# Versie_1.net
KiCad netlist of a schematic drawn in EAGLE
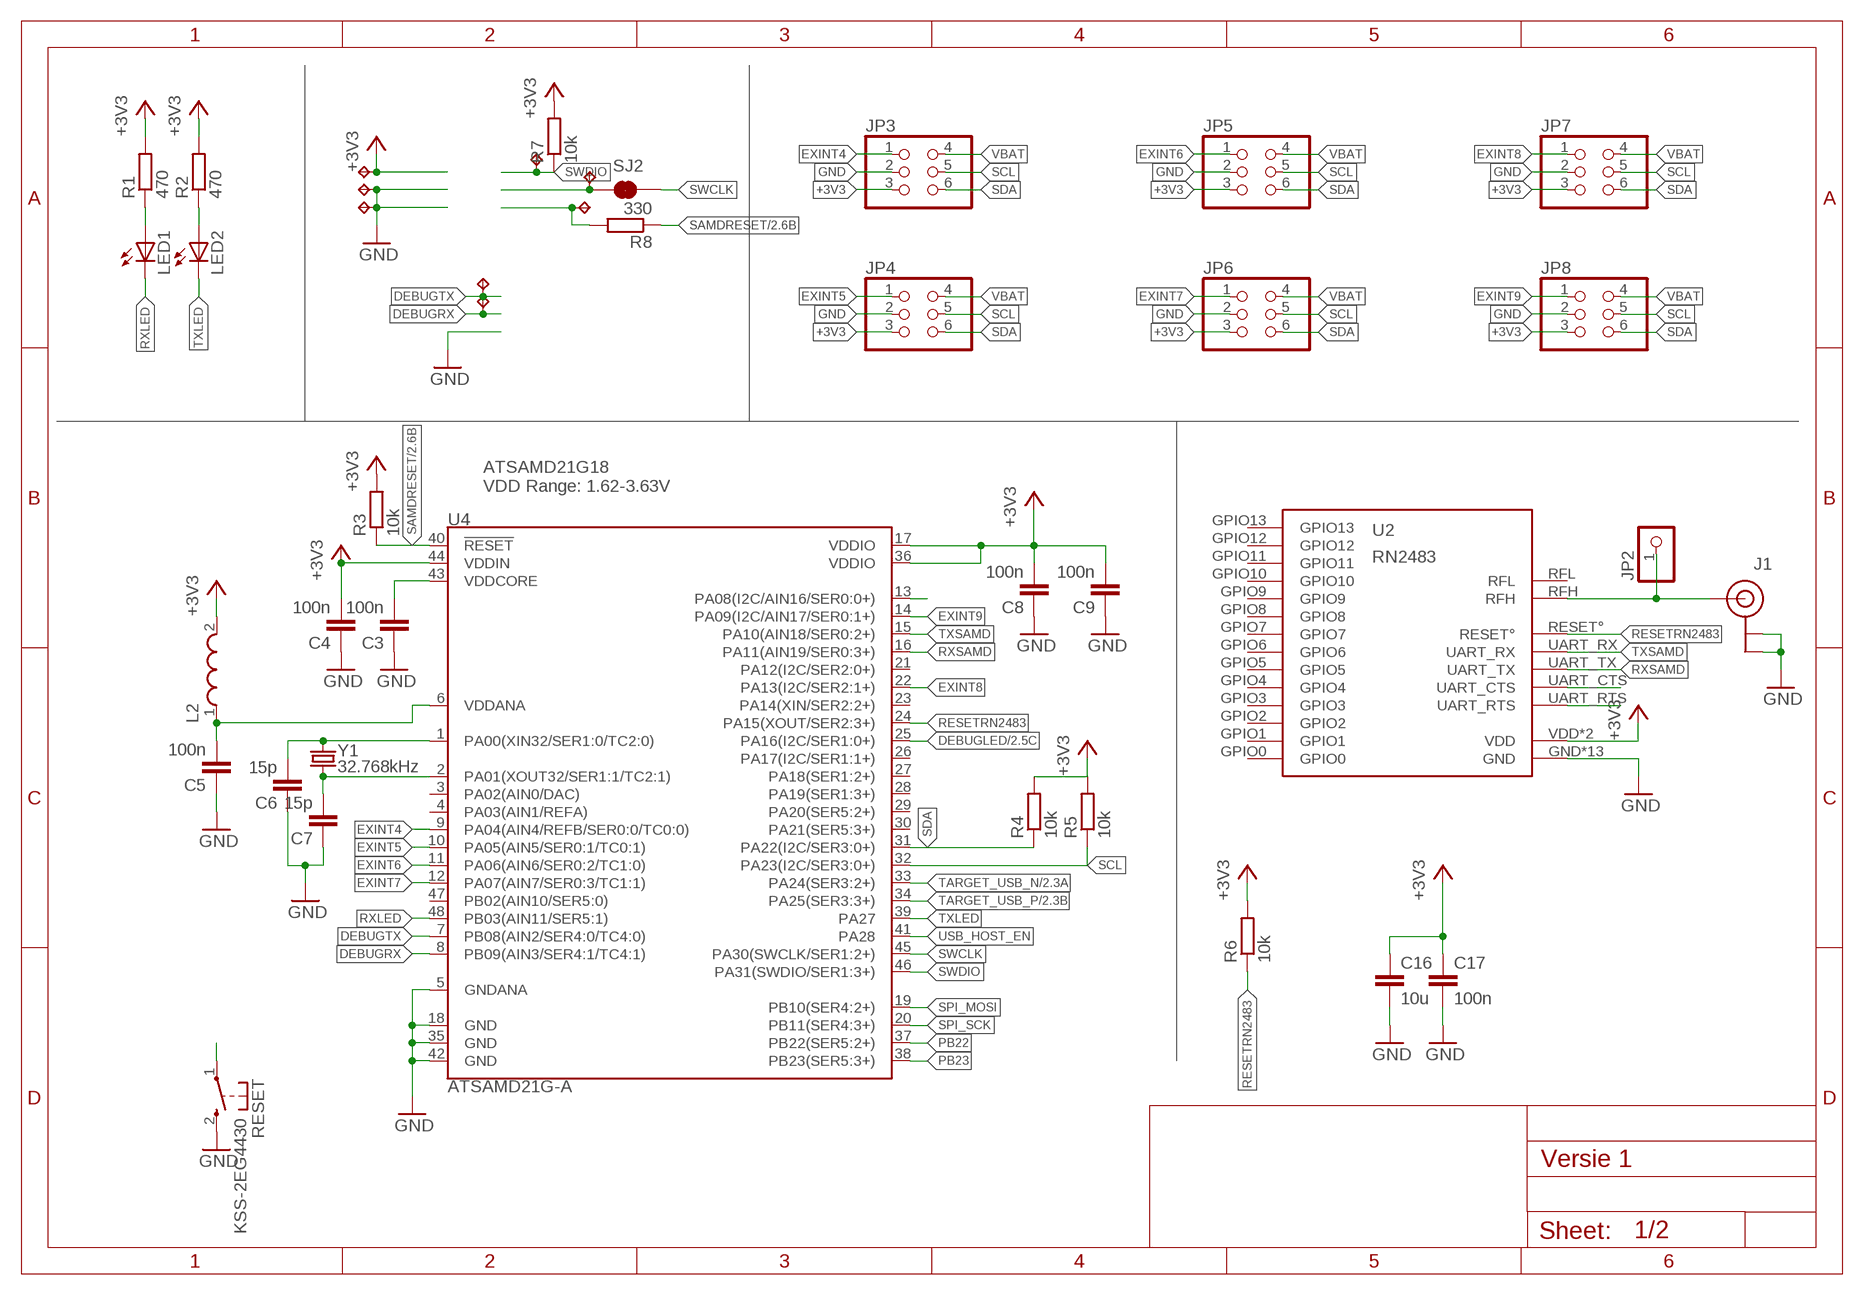
[diagram p0: schematic, sheet 1]
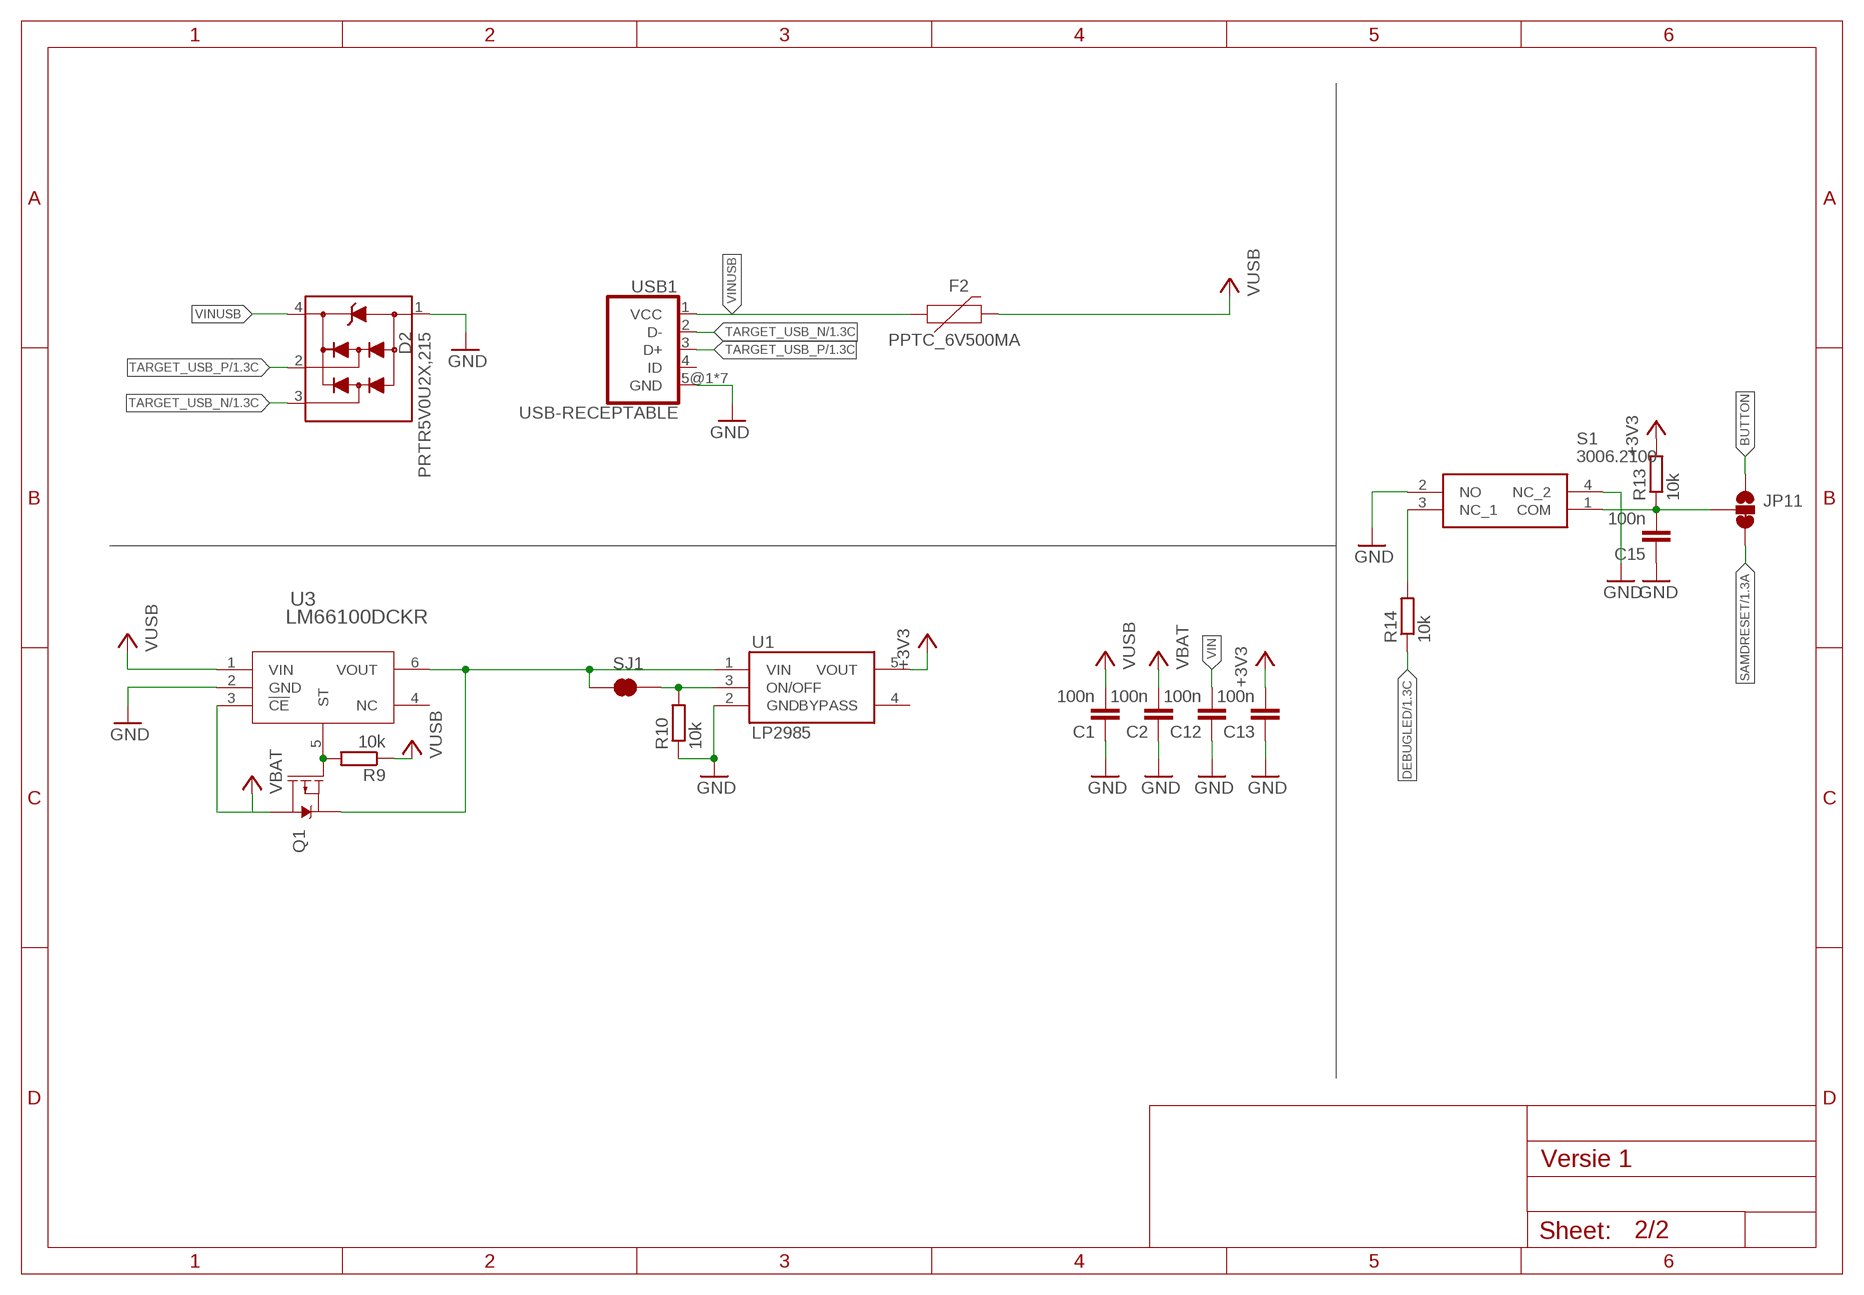
[diagram p1: schematic, sheet 2]

(export (version "E")
  (design (tool "Eeschema 10.0.6"))
  (components
    (comp (ref "C1")
      (value "100n")
      (footprint "eagle-import:C0603")
      (libsource (lib "eagle-import") (part "C-EUC0603"))
    )
    (comp (ref "C2")
      (value "100n")
      (footprint "eagle-import:C0603")
      (libsource (lib "eagle-import") (part "C-EUC0603"))
    )
    (comp (ref "C12")
      (value "100n")
      (footprint "eagle-import:C0603")
      (libsource (lib "eagle-import") (part "C-EUC0603"))
    )
    (comp (ref "C13")
      (value "100n")
      (footprint "eagle-import:C0603")
      (libsource (lib "eagle-import") (part "C-EUC0603"))
    )
    (comp (ref "C15")
      (value "100n")
      (footprint "eagle-import:C0603")
      (libsource (lib "eagle-import") (part "C-EUC0603"))
    )
    (comp (ref "D2")
      (value "PRTR5V0U2X,215")
      (footprint "eagle-import:SOT143B")
      (fields (field (name "MF") "Nexperia USA Inc."))
      (libsource (lib "eagle-import") (part "PRTR5V0U2X,215"))
    )
    (comp (ref "F2")
      (value "PPTC_6V500MA")
      (footprint "eagle-import:0805")
      (libsource (lib "eagle-import") (part "PPTC_6V500MA"))
    )
    (comp (ref "JP11")
      (value "JUMPER-SMT_3_1-NC_TRACE_SILK")
      (footprint "eagle-import:SMT-JUMPER_3_1-NC_TRACE_SILK")
      (libsource (lib "eagle-import") (part "JUMPER-SMT_3_1-NC_TRACE_SILK"))
    )
    (comp (ref "Q1")
      (value "MOSFET_PCH-DMG2307L")
      (footprint "eagle-import:SOT23-3")
      (libsource (lib "eagle-import") (part "MOSFET_PCH-DMG2307L"))
    )
    (comp (ref "R9")
      (value "10k")
      (footprint "eagle-import:R0603")
      (libsource (lib "eagle-import") (part "R-EU_R0603"))
    )
    (comp (ref "R10")
      (value "10k")
      (footprint "eagle-import:R0603")
      (libsource (lib "eagle-import") (part "R-EU_R0603"))
    )
    (comp (ref "R13")
      (value "10k")
      (footprint "eagle-import:R0603")
      (libsource (lib "eagle-import") (part "R-EU_R0603"))
    )
    (comp (ref "R14")
      (value "10k")
      (footprint "eagle-import:R0603")
      (libsource (lib "eagle-import") (part "R-EU_R0603"))
    )
    (comp (ref "S1")
      (value "3006.2100")
      (footprint "eagle-import:30062101")
      (fields (field (name "MOUSER_PART_NUMBER") "979-3006.2100"))
      (libsource (lib "eagle-import") (part "3006.2100"))
    )
    (comp (ref "SJ1")
      (value "JUMPER-PAD-2-NC_BY_TRACENO_SILK")
      (footprint "eagle-import:PAD-JUMPER-2-NC_BY_TRACE_NO_SILK")
      (libsource (lib "eagle-import") (part "JUMPER-PAD-2-NC_BY_TRACENO_SILK"))
    )
    (comp (ref "U1")
      (value "LP2985AIM5-3.3")
      (footprint "eagle-import:SOT25")
      (libsource (lib "eagle-import") (part "LP2985AIM5-3.3"))
    )
    (comp (ref "U3")
      (value "LM66100DCKR")
      (footprint "eagle-import:DCK6_TEX")
      (fields (field (name "COPYRIGHT") "Copyright (C) 2018 Accelerated Designs. All rights reserved"))
      (libsource (lib "eagle-import") (part "LM66100DCKR"))
    )
    (comp (ref "USB1")
      (value "USB-RECEPTABLE")
      (footprint "eagle-import:FCI-10103594-0001LF")
      (libsource (lib "eagle-import") (part "USB-RECEPTABLE"))
    )
    (comp (ref "C3")
      (value "100n")
      (footprint "eagle-import:C0603")
      (libsource (lib "eagle-import") (part "C-EUC0603"))
    )
    (comp (ref "C4")
      (value "100n")
      (footprint "eagle-import:C0603")
      (libsource (lib "eagle-import") (part "C-EUC0603"))
    )
    (comp (ref "C5")
      (value "100n")
      (footprint "eagle-import:C0603")
      (libsource (lib "eagle-import") (part "C-EUC0603"))
    )
    (comp (ref "C6")
      (value "15p")
      (footprint "eagle-import:C0603")
      (libsource (lib "eagle-import") (part "C-EUC0603"))
    )
    (comp (ref "C7")
      (value "15p")
      (footprint "eagle-import:C0603")
      (libsource (lib "eagle-import") (part "C-EUC0603"))
    )
    (comp (ref "C8")
      (value "100n")
      (footprint "eagle-import:C0603")
      (libsource (lib "eagle-import") (part "C-EUC0603"))
    )
    (comp (ref "C9")
      (value "100n")
      (footprint "eagle-import:C0603")
      (libsource (lib "eagle-import") (part "C-EUC0603"))
    )
    (comp (ref "C16")
      (value "10u")
      (footprint "eagle-import:C0805")
      (libsource (lib "eagle-import") (part "C-EUC0805"))
    )
    (comp (ref "C17")
      (value "100n")
      (footprint "eagle-import:C0603")
      (libsource (lib "eagle-import") (part "C-EUC0603"))
    )
    (comp (ref "J1")
      (value "U.FL")
      (footprint "eagle-import:U.FL")
      (libsource (lib "eagle-import") (part "U.FL"))
    )
    (comp (ref "JP2")
      (value "PINHD-1X1")
      (footprint "eagle-import:1X01")
      (libsource (lib "eagle-import") (part "PINHD-1X1"))
    )
    (comp (ref "JP3")
      (value "PINHD-2X3")
      (footprint "eagle-import:2X03")
      (libsource (lib "eagle-import") (part "PINHD-2X3"))
    )
    (comp (ref "JP4")
      (value "PINHD-2X3")
      (footprint "eagle-import:2X03")
      (libsource (lib "eagle-import") (part "PINHD-2X3"))
    )
    (comp (ref "JP5")
      (value "PINHD-2X3")
      (footprint "eagle-import:2X03")
      (libsource (lib "eagle-import") (part "PINHD-2X3"))
    )
    (comp (ref "JP6")
      (value "PINHD-2X3")
      (footprint "eagle-import:2X03")
      (libsource (lib "eagle-import") (part "PINHD-2X3"))
    )
    (comp (ref "JP7")
      (value "PINHD-2X3")
      (footprint "eagle-import:2X03")
      (libsource (lib "eagle-import") (part "PINHD-2X3"))
    )
    (comp (ref "JP8")
      (value "PINHD-2X3")
      (footprint "eagle-import:2X03")
      (libsource (lib "eagle-import") (part "PINHD-2X3"))
    )
    (comp (ref "L2")
      (value "WE-CBA_0603(WB/HS)")
      (footprint "eagle-import:WE-CBA_0603(W=2.2)")
      (libsource (lib "eagle-import") (part "WE-CBA_0603(WB/HS)"))
    )
    (comp (ref "LED1")
      (value "LEDCHIP-LED0603")
      (footprint "eagle-import:CHIP-LED0603")
      (libsource (lib "eagle-import") (part "LEDCHIP-LED0603"))
    )
    (comp (ref "LED2")
      (value "LEDCHIP-LED0603")
      (footprint "eagle-import:CHIP-LED0603")
      (libsource (lib "eagle-import") (part "LEDCHIP-LED0603"))
    )
    (comp (ref "R1")
      (value "470")
      (footprint "eagle-import:R0603")
      (libsource (lib "eagle-import") (part "R-EU_R0603"))
    )
    (comp (ref "R2")
      (value "470")
      (footprint "eagle-import:R0603")
      (libsource (lib "eagle-import") (part "R-EU_R0603"))
    )
    (comp (ref "R3")
      (value "10k")
      (footprint "eagle-import:R0603")
      (libsource (lib "eagle-import") (part "R-EU_R0603"))
    )
    (comp (ref "R4")
      (value "10k")
      (footprint "eagle-import:R0603")
      (libsource (lib "eagle-import") (part "R-EU_R0603"))
    )
    (comp (ref "R5")
      (value "10k")
      (footprint "eagle-import:R0603")
      (libsource (lib "eagle-import") (part "R-EU_R0603"))
    )
    (comp (ref "R6")
      (value "10k")
      (footprint "eagle-import:R0603")
      (libsource (lib "eagle-import") (part "R-EU_R0603"))
    )
    (comp (ref "R7")
      (value "10k")
      (footprint "eagle-import:R0603")
      (libsource (lib "eagle-import") (part "R-EU_R0603"))
    )
    (comp (ref "R8")
      (value "330")
      (footprint "eagle-import:R0603")
      (libsource (lib "eagle-import") (part "R-EU_R0603"))
    )
    (comp (ref "RESET")
      (value "KSS-2EG4430")
      (footprint "eagle-import:KSS-2EG4430")
      (libsource (lib "eagle-import") (part "KSS-2EG4430"))
    )
    (comp (ref "SJ2")
      (value "JUMPER-PAD-2-NC_BY_TRACENO_SILK")
      (footprint "eagle-import:PAD-JUMPER-2-NC_BY_TRACE_NO_SILK")
      (libsource (lib "eagle-import") (part "JUMPER-PAD-2-NC_BY_TRACENO_SILK"))
    )
    (comp (ref "TP1")
      (value "TPB1,27")
      (footprint "eagle-import:B1,27")
      (libsource (lib "eagle-import") (part "TPB1,27"))
    )
    (comp (ref "TP2")
      (value "TPB1,27")
      (footprint "eagle-import:B1,27")
      (libsource (lib "eagle-import") (part "TPB1,27"))
    )
    (comp (ref "TP3")
      (value "TPB1,27")
      (footprint "eagle-import:B1,27")
      (libsource (lib "eagle-import") (part "TPB1,27"))
    )
    (comp (ref "TP4")
      (value "TPB1,27")
      (footprint "eagle-import:B1,27")
      (libsource (lib "eagle-import") (part "TPB1,27"))
    )
    (comp (ref "TP5")
      (value "TPB1,27")
      (footprint "eagle-import:B1,27")
      (libsource (lib "eagle-import") (part "TPB1,27"))
    )
    (comp (ref "TP6")
      (value "TPB1,27")
      (footprint "eagle-import:B1,27")
      (libsource (lib "eagle-import") (part "TPB1,27"))
    )
    (comp (ref "TP7")
      (value "TPB1,27")
      (footprint "eagle-import:B1,27")
      (libsource (lib "eagle-import") (part "TPB1,27"))
    )
    (comp (ref "TP8")
      (value "TPB1,27")
      (footprint "eagle-import:B1,27")
      (libsource (lib "eagle-import") (part "TPB1,27"))
    )
    (comp (ref "U2")
      (value "RN2483")
      (footprint "eagle-import:RN2483")
      (libsource (lib "eagle-import") (part "RN2483"))
    )
    (comp (ref "U4")
      (value "ATSAMD21G-A")
      (footprint "eagle-import:TQFP-48")
      (libsource (lib "eagle-import") (part "ATSAMD21G-A"))
    )
    (comp (ref "Y1")
      (value "32.768kHz")
      (footprint "eagle-import:CRYSTAL-SMD-3.2X1.5MM")
      (libsource (lib "eagle-import") (part "CRYSTAL3.2X1.5MM"))
    )
  )
  (nets
    (net (code "1") (name "+3V3") (class "Default")
      (node (ref "C13") (pin "2") (pinfunction "2_2") (pintype "passive"))
      (node (ref "C16") (pin "1") (pinfunction "1_1") (pintype "passive"))
      (node (ref "C17") (pin "1") (pinfunction "1_1") (pintype "passive"))
      (node (ref "C4") (pin "2") (pinfunction "2_2") (pintype "passive"))
      (node (ref "C8") (pin "2") (pinfunction "2_2") (pintype "passive"))
      (node (ref "C9") (pin "2") (pinfunction "2_2") (pintype "passive"))
      (node (ref "JP3") (pin "3") (pinfunction "3_3") (pintype "passive"))
      (node (ref "JP4") (pin "3") (pinfunction "3_3") (pintype "passive"))
      (node (ref "JP5") (pin "3") (pinfunction "3_3") (pintype "passive"))
      (node (ref "JP6") (pin "3") (pinfunction "3_3") (pintype "passive"))
      (node (ref "JP7") (pin "3") (pinfunction "3_3") (pintype "passive"))
      (node (ref "JP8") (pin "3") (pinfunction "3_3") (pintype "passive"))
      (node (ref "L2") (pin "2") (pinfunction "2_2") (pintype "passive"))
      (node (ref "R1") (pin "2") (pinfunction "2_2") (pintype "passive"))
      (node (ref "R13") (pin "2") (pinfunction "2_2") (pintype "passive"))
      (node (ref "R2") (pin "2") (pinfunction "2_2") (pintype "passive"))
      (node (ref "R3") (pin "2") (pinfunction "2_2") (pintype "passive"))
      (node (ref "R4") (pin "2") (pinfunction "2_2") (pintype "passive"))
      (node (ref "R5") (pin "2") (pinfunction "2_2") (pintype "passive"))
      (node (ref "R6") (pin "2") (pinfunction "2_2") (pintype "passive"))
      (node (ref "R7") (pin "2") (pinfunction "2_2") (pintype "passive"))
      (node (ref "TP1") (pin "TP") (pinfunction "TP_TP") (pintype "input"))
      (node (ref "U1") (pin "5") (pinfunction "VOUT_5") (pintype "power_in"))
      (node (ref "U2") (pin "VDD") (pinfunction "VDD_VDD") (pintype "bidirectional"))
      (node (ref "U2") (pin "VDD2") (pinfunction "VDD_VDD2") (pintype "bidirectional"))
      (node (ref "U4") (pin "17") (pinfunction "VDDIO_17") (pintype "bidirectional"))
      (node (ref "U4") (pin "36") (pinfunction "VDDIO_36") (pintype "bidirectional"))
      (node (ref "U4") (pin "44") (pinfunction "VDDIN_44") (pintype "bidirectional"))
    )
    (net (code "2") (name "BUTTON") (class "Default")
      (node (ref "JP11") (pin "1") (pinfunction "1_1") (pintype "passive"))
      (node (ref "U4") (pin "13") (pinfunction "PA08(I2C/AIN16/SER0:0+)_13") (pintype "bidirectional"))
    )
    (net (code "3") (name "BYPASS") (class "Default")
      (node (ref "U1") (pin "4") (pinfunction "BYPASS_4") (pintype "power_in"))
    )
    (net (code "4") (name "DEBUGLED") (class "Default")
      (node (ref "R14") (pin "1") (pinfunction "1_1") (pintype "passive"))
      (node (ref "U4") (pin "25") (pinfunction "PA16(I2C/SER1:0+)_25") (pintype "bidirectional"))
    )
    (net (code "5") (name "DEBUGRX") (class "Default")
      (node (ref "TP8") (pin "TP") (pinfunction "TP_TP") (pintype "input"))
      (node (ref "U4") (pin "8") (pinfunction "PB09(AIN3/SER4:1/TC4:1)_8") (pintype "bidirectional"))
    )
    (net (code "6") (name "DEBUGTX") (class "Default")
      (node (ref "TP7") (pin "TP") (pinfunction "TP_TP") (pintype "input"))
      (node (ref "U4") (pin "7") (pinfunction "PB08(AIN2/SER4:0/TC4:0)_7") (pintype "bidirectional"))
    )
    (net (code "7") (name "EXINT4") (class "Default")
      (node (ref "JP3") (pin "1") (pinfunction "1_1") (pintype "passive"))
      (node (ref "U4") (pin "9") (pinfunction "PA04(AIN4/REFB/SER0:0/TC0:0)_9") (pintype "bidirectional"))
    )
    (net (code "8") (name "EXINT5") (class "Default")
      (node (ref "JP4") (pin "1") (pinfunction "1_1") (pintype "passive"))
      (node (ref "U4") (pin "10") (pinfunction "PA05(AIN5/SER0:1/TC0:1)_10") (pintype "bidirectional"))
    )
    (net (code "9") (name "EXINT6") (class "Default")
      (node (ref "JP5") (pin "1") (pinfunction "1_1") (pintype "passive"))
      (node (ref "U4") (pin "11") (pinfunction "PA06(AIN6/SER0:2/TC1:0)_11") (pintype "bidirectional"))
    )
    (net (code "10") (name "EXINT7") (class "Default")
      (node (ref "JP6") (pin "1") (pinfunction "1_1") (pintype "passive"))
      (node (ref "U4") (pin "12") (pinfunction "PA07(AIN7/SER0:3/TC1:1)_12") (pintype "bidirectional"))
    )
    (net (code "11") (name "EXINT8") (class "Default")
      (node (ref "JP7") (pin "1") (pinfunction "1_1") (pintype "passive"))
      (node (ref "U4") (pin "22") (pinfunction "PA13(I2C/SER2:1+)_22") (pintype "bidirectional"))
    )
    (net (code "12") (name "EXINT9") (class "Default")
      (node (ref "JP8") (pin "1") (pinfunction "1_1") (pintype "passive"))
      (node (ref "U4") (pin "14") (pinfunction "PA09(I2C/AIN17/SER0:1+)_14") (pintype "bidirectional"))
    )
    (net (code "13") (name "GND") (class "Default")
      (node (ref "C1") (pin "1") (pinfunction "1_1") (pintype "passive"))
      (node (ref "C12") (pin "1") (pinfunction "1_1") (pintype "passive"))
      (node (ref "C13") (pin "1") (pinfunction "1_1") (pintype "passive"))
      (node (ref "C15") (pin "1") (pinfunction "1_1") (pintype "passive"))
      (node (ref "C16") (pin "2") (pinfunction "2_2") (pintype "passive"))
      (node (ref "C17") (pin "2") (pinfunction "2_2") (pintype "passive"))
      (node (ref "C2") (pin "1") (pinfunction "1_1") (pintype "passive"))
      (node (ref "C3") (pin "1") (pinfunction "1_1") (pintype "passive"))
      (node (ref "C4") (pin "1") (pinfunction "1_1") (pintype "passive"))
      (node (ref "C5") (pin "1") (pinfunction "1_1") (pintype "passive"))
      (node (ref "C6") (pin "1") (pinfunction "1_1") (pintype "passive"))
      (node (ref "C7") (pin "1") (pinfunction "1_1") (pintype "passive"))
      (node (ref "C8") (pin "1") (pinfunction "1_1") (pintype "passive"))
      (node (ref "C9") (pin "1") (pinfunction "1_1") (pintype "passive"))
      (node (ref "D2") (pin "1") (pinfunction "P$1_1") (pintype "passive"))
      (node (ref "J1") (pin "P$1") (pinfunction "GND_P$1") (pintype "bidirectional"))
      (node (ref "J1") (pin "P$2") (pinfunction "GND_P$2") (pintype "bidirectional"))
      (node (ref "JP3") (pin "2") (pinfunction "2_2") (pintype "passive"))
      (node (ref "JP4") (pin "2") (pinfunction "2_2") (pintype "passive"))
      (node (ref "JP5") (pin "2") (pinfunction "2_2") (pintype "passive"))
      (node (ref "JP6") (pin "2") (pinfunction "2_2") (pintype "passive"))
      (node (ref "JP7") (pin "2") (pinfunction "2_2") (pintype "passive"))
      (node (ref "JP8") (pin "2") (pinfunction "2_2") (pintype "passive"))
      (node (ref "R10") (pin "1") (pinfunction "1_1") (pintype "passive"))
      (node (ref "RESET") (pin "2") (pinfunction "S_2") (pintype "passive"))
      (node (ref "S1") (pin "2") (pinfunction "NO_2") (pintype "bidirectional"))
      (node (ref "S1") (pin "4") (pinfunction "NC_2_4") (pintype "bidirectional"))
      (node (ref "TP2") (pin "TP") (pinfunction "TP_TP") (pintype "input"))
      (node (ref "TP3") (pin "TP") (pinfunction "TP_TP") (pintype "input"))
      (node (ref "U1") (pin "2") (pinfunction "GND_2") (pintype "power_in"))
      (node (ref "U2") (pin "GND") (pinfunction "GND_GND") (pintype "bidirectional"))
      (node (ref "U2") (pin "GND1") (pinfunction "GND_GND1") (pintype "bidirectional"))
      (node (ref "U2") (pin "GND10") (pinfunction "GND_GND10") (pintype "bidirectional"))
      (node (ref "U2") (pin "GND11") (pinfunction "GND_GND11") (pintype "bidirectional"))
      (node (ref "U2") (pin "GND12") (pinfunction "GND_GND12") (pintype "bidirectional"))
      (node (ref "U2") (pin "GND2") (pinfunction "GND_GND2") (pintype "bidirectional"))
      (node (ref "U2") (pin "GND3") (pinfunction "GND_GND3") (pintype "bidirectional"))
      (node (ref "U2") (pin "GND4") (pinfunction "GND_GND4") (pintype "bidirectional"))
      (node (ref "U2") (pin "GND5") (pinfunction "GND_GND5") (pintype "bidirectional"))
      (node (ref "U2") (pin "GND6") (pinfunction "GND_GND6") (pintype "bidirectional"))
      (node (ref "U2") (pin "GND7") (pinfunction "GND_GND7") (pintype "bidirectional"))
      (node (ref "U2") (pin "GND8") (pinfunction "GND_GND8") (pintype "bidirectional"))
      (node (ref "U2") (pin "GND9") (pinfunction "GND_GND9") (pintype "bidirectional"))
      (node (ref "U3") (pin "2") (pinfunction "GND_2") (pintype "power_in"))
      (node (ref "U4") (pin "18") (pinfunction "GND_18") (pintype "bidirectional"))
      (node (ref "U4") (pin "35") (pinfunction "GND_35") (pintype "bidirectional"))
      (node (ref "U4") (pin "42") (pinfunction "GND_42") (pintype "bidirectional"))
      (node (ref "U4") (pin "5") (pinfunction "GNDANA_5") (pintype "bidirectional"))
      (node (ref "USB1") (pin "5@1") (pinfunction "GND_5@1") (pintype "bidirectional"))
      (node (ref "USB1") (pin "5@2") (pinfunction "GND_5@2") (pintype "bidirectional"))
      (node (ref "USB1") (pin "5@3") (pinfunction "GND_5@3") (pintype "bidirectional"))
      (node (ref "USB1") (pin "5@4") (pinfunction "GND_5@4") (pintype "bidirectional"))
      (node (ref "USB1") (pin "5@5") (pinfunction "GND_5@5") (pintype "bidirectional"))
      (node (ref "USB1") (pin "5@6") (pinfunction "GND_5@6") (pintype "bidirectional"))
      (node (ref "USB1") (pin "5@7") (pinfunction "GND_5@7") (pintype "bidirectional"))
    )
    (net (code "14") (name "Net-(J1-SIGNAL)") (class "Default")
      (node (ref "J1") (pin "P$3") (pinfunction "SIGNAL_P$3") (pintype "bidirectional"))
      (node (ref "JP2") (pin "1") (pinfunction "1_1") (pintype "passive"))
      (node (ref "U2") (pin "RFH") (pinfunction "RFH_RFH") (pintype "bidirectional"))
    )
    (net (code "15") (name "Net-(LED1-PadA)") (class "Default")
      (node (ref "LED1") (pin "A") (pinfunction "A_A") (pintype "passive"))
      (node (ref "R1") (pin "1") (pinfunction "1_1") (pintype "passive"))
    )
    (net (code "16") (name "Net-(LED2-PadA)") (class "Default")
      (node (ref "LED2") (pin "A") (pinfunction "A_A") (pintype "passive"))
      (node (ref "R2") (pin "1") (pinfunction "1_1") (pintype "passive"))
    )
    (net (code "17") (name "Net-(Q1-G)") (class "Default")
      (node (ref "Q1") (pin "1") (pinfunction "G_1") (pintype "bidirectional"))
      (node (ref "R9") (pin "2") (pinfunction "2_2") (pintype "passive"))
      (node (ref "U3") (pin "5") (pinfunction "ST_5") (pintype "output"))
    )
    (net (code "18") (name "Net-(R8-Pad2)") (class "Default")
      (node (ref "R8") (pin "2") (pinfunction "2_2") (pintype "passive"))
      (node (ref "TP6") (pin "TP") (pinfunction "TP_TP") (pintype "input"))
    )
    (net (code "19") (name "Net-(S1-COM)") (class "Default")
      (node (ref "C15") (pin "2") (pinfunction "2_2") (pintype "passive"))
      (node (ref "JP11") (pin "2") (pinfunction "2_2") (pintype "passive"))
      (node (ref "R13") (pin "1") (pinfunction "1_1") (pintype "passive"))
      (node (ref "S1") (pin "1") (pinfunction "COM_1") (pintype "bidirectional"))
    )
    (net (code "20") (name "Net-(S1-NC_1)") (class "Default")
      (node (ref "R14") (pin "2") (pinfunction "2_2") (pintype "passive"))
      (node (ref "S1") (pin "3") (pinfunction "NC_1_3") (pintype "bidirectional"))
    )
    (net (code "21") (name "Net-(SJ2-Pad2)") (class "Default")
      (node (ref "SJ2") (pin "2") (pinfunction "2_2") (pintype "passive"))
      (node (ref "TP5") (pin "TP") (pinfunction "TP_TP") (pintype "input"))
    )
    (net (code "22") (name "Net-(U1-ON{slash}OFF)") (class "Default")
      (node (ref "R10") (pin "2") (pinfunction "2_2") (pintype "passive"))
      (node (ref "SJ1") (pin "1") (pinfunction "1_1") (pintype "passive"))
      (node (ref "U1") (pin "3") (pinfunction "ON/OFF_3") (pintype "input"))
    )
    (net (code "23") (name "Net-(U4-PA00(XIN32{slash}SER1:0{slash}TC2:0))") (class "Default")
      (node (ref "C6") (pin "2") (pinfunction "2_2") (pintype "passive"))
      (node (ref "U4") (pin "1") (pinfunction "PA00(XIN32/SER1:0/TC2:0)_1") (pintype "bidirectional"))
      (node (ref "Y1") (pin "P$2") (pinfunction "2_P$2") (pintype "passive"))
    )
    (net (code "24") (name "Net-(U4-PA01(XOUT32{slash}SER1:1{slash}TC2:1))") (class "Default")
      (node (ref "C7") (pin "2") (pinfunction "2_2") (pintype "passive"))
      (node (ref "U4") (pin "2") (pinfunction "PA01(XOUT32/SER1:1/TC2:1)_2") (pintype "bidirectional"))
      (node (ref "Y1") (pin "P$1") (pinfunction "1_P$1") (pintype "passive"))
    )
    (net (code "25") (name "Net-(U4-VDDANA)") (class "Default")
      (node (ref "C5") (pin "2") (pinfunction "2_2") (pintype "passive"))
      (node (ref "L2") (pin "1") (pinfunction "1_1") (pintype "passive"))
      (node (ref "U4") (pin "6") (pinfunction "VDDANA_6") (pintype "bidirectional"))
    )
    (net (code "26") (name "Net-(U4-VDDCORE)") (class "Default")
      (node (ref "C3") (pin "2") (pinfunction "2_2") (pintype "passive"))
      (node (ref "U4") (pin "43") (pinfunction "VDDCORE_43") (pintype "bidirectional"))
    )
    (net (code "27") (name "PB22") (class "Default")
      (node (ref "U4") (pin "37") (pinfunction "PB22(SER5:2+)_37") (pintype "bidirectional"))
    )
    (net (code "28") (name "PB23") (class "Default")
      (node (ref "U4") (pin "38") (pinfunction "PB23(SER5:3+)_38") (pintype "bidirectional"))
    )
    (net (code "29") (name "RESETRN2483") (class "Default")
      (node (ref "R6") (pin "1") (pinfunction "1_1") (pintype "passive"))
      (node (ref "U2") (pin "RESET°") (pinfunction "RESET°_RESET°") (pintype "bidirectional"))
      (node (ref "U4") (pin "24") (pinfunction "PA15(XOUT/SER2:3+)_24") (pintype "bidirectional"))
    )
    (net (code "30") (name "RXLED") (class "Default")
      (node (ref "LED1") (pin "C") (pinfunction "C_C") (pintype "passive"))
      (node (ref "U4") (pin "48") (pinfunction "PB03(AIN11/SER5:1)_48") (pintype "bidirectional"))
    )
    (net (code "31") (name "RXSAMD") (class "Default")
      (node (ref "U2") (pin "UART_TX") (pinfunction "UART_TX_UART_TX") (pintype "bidirectional"))
      (node (ref "U4") (pin "16") (pinfunction "PA11(AIN19/SER0:3+)_16") (pintype "bidirectional"))
    )
    (net (code "32") (name "SAMDRESET") (class "Default")
      (node (ref "JP11") (pin "3") (pinfunction "3_3") (pintype "passive"))
      (node (ref "R3") (pin "1") (pinfunction "1_1") (pintype "passive"))
      (node (ref "R8") (pin "1") (pinfunction "1_1") (pintype "passive"))
      (node (ref "RESET") (pin "1") (pinfunction "P_1") (pintype "passive"))
      (node (ref "U4") (pin "40") (pinfunction "~{RESET}_40") (pintype "bidirectional"))
    )
    (net (code "33") (name "SCL") (class "Default")
      (node (ref "JP3") (pin "5") (pinfunction "5_5") (pintype "passive"))
      (node (ref "JP4") (pin "5") (pinfunction "5_5") (pintype "passive"))
      (node (ref "JP5") (pin "5") (pinfunction "5_5") (pintype "passive"))
      (node (ref "JP6") (pin "5") (pinfunction "5_5") (pintype "passive"))
      (node (ref "JP7") (pin "5") (pinfunction "5_5") (pintype "passive"))
      (node (ref "JP8") (pin "5") (pinfunction "5_5") (pintype "passive"))
      (node (ref "R5") (pin "1") (pinfunction "1_1") (pintype "passive"))
      (node (ref "U4") (pin "32") (pinfunction "PA23(I2C/SER3:0+)_32") (pintype "bidirectional"))
    )
    (net (code "34") (name "SDA") (class "Default")
      (node (ref "JP3") (pin "6") (pinfunction "6_6") (pintype "passive"))
      (node (ref "JP4") (pin "6") (pinfunction "6_6") (pintype "passive"))
      (node (ref "JP5") (pin "6") (pinfunction "6_6") (pintype "passive"))
      (node (ref "JP6") (pin "6") (pinfunction "6_6") (pintype "passive"))
      (node (ref "JP7") (pin "6") (pinfunction "6_6") (pintype "passive"))
      (node (ref "JP8") (pin "6") (pinfunction "6_6") (pintype "passive"))
      (node (ref "R4") (pin "1") (pinfunction "1_1") (pintype "passive"))
      (node (ref "U4") (pin "31") (pinfunction "PA22(I2C/SER3:0+)_31") (pintype "bidirectional"))
    )
    (net (code "35") (name "SPI_MOSI") (class "Default")
      (node (ref "U4") (pin "19") (pinfunction "PB10(SER4:2+)_19") (pintype "bidirectional"))
    )
    (net (code "36") (name "SPI_SCK") (class "Default")
      (node (ref "U4") (pin "20") (pinfunction "PB11(SER4:3+)_20") (pintype "bidirectional"))
    )
    (net (code "37") (name "SWCLK") (class "Default")
      (node (ref "SJ2") (pin "1") (pinfunction "1_1") (pintype "passive"))
      (node (ref "U4") (pin "45") (pinfunction "PA30(SWCLK/SER1:2+)_45") (pintype "bidirectional"))
    )
    (net (code "38") (name "SWDIO") (class "Default")
      (node (ref "R7") (pin "1") (pinfunction "1_1") (pintype "passive"))
      (node (ref "TP4") (pin "TP") (pinfunction "TP_TP") (pintype "input"))
      (node (ref "U4") (pin "46") (pinfunction "PA31(SWDIO/SER1:3+)_46") (pintype "bidirectional"))
    )
    (net (code "39") (name "TARGET_USB_N") (class "Default")
      (node (ref "D2") (pin "3") (pinfunction "P$3_3") (pintype "passive"))
      (node (ref "U4") (pin "33") (pinfunction "PA24(SER3:2+)_33") (pintype "bidirectional"))
      (node (ref "USB1") (pin "2") (pinfunction "D-_2") (pintype "bidirectional"))
    )
    (net (code "40") (name "TARGET_USB_P") (class "Default")
      (node (ref "D2") (pin "2") (pinfunction "P$2_2") (pintype "passive"))
      (node (ref "U4") (pin "34") (pinfunction "PA25(SER3:3+)_34") (pintype "bidirectional"))
      (node (ref "USB1") (pin "3") (pinfunction "D+_3") (pintype "bidirectional"))
    )
    (net (code "41") (name "TXLED") (class "Default")
      (node (ref "LED2") (pin "C") (pinfunction "C_C") (pintype "passive"))
      (node (ref "U4") (pin "39") (pinfunction "PA27_39") (pintype "bidirectional"))
    )
    (net (code "42") (name "TXSAMD") (class "Default")
      (node (ref "U2") (pin "UART_RX") (pinfunction "UART_RX_UART_RX") (pintype "bidirectional"))
      (node (ref "U4") (pin "15") (pinfunction "PA10(AIN18/SER0:2+)_15") (pintype "bidirectional"))
    )
    (net (code "43") (name "USB_HOST_EN") (class "Default")
      (node (ref "U4") (pin "41") (pinfunction "PA28_41") (pintype "bidirectional"))
    )
    (net (code "44") (name "VBAT") (class "Default")
      (node (ref "C2") (pin "2") (pinfunction "2_2") (pintype "passive"))
      (node (ref "JP3") (pin "4") (pinfunction "4_4") (pintype "passive"))
      (node (ref "JP4") (pin "4") (pinfunction "4_4") (pintype "passive"))
      (node (ref "JP5") (pin "4") (pinfunction "4_4") (pintype "passive"))
      (node (ref "JP6") (pin "4") (pinfunction "4_4") (pintype "passive"))
      (node (ref "JP7") (pin "4") (pinfunction "4_4") (pintype "passive"))
      (node (ref "JP8") (pin "4") (pinfunction "4_4") (pintype "passive"))
      (node (ref "Q1") (pin "3") (pinfunction "D_3") (pintype "bidirectional"))
      (node (ref "U3") (pin "3") (pinfunction "~{CE}_3") (pintype "input"))
    )
    (net (code "45") (name "VIN") (class "Default")
      (node (ref "C12") (pin "2") (pinfunction "2_2") (pintype "passive"))
      (node (ref "Q1") (pin "2") (pinfunction "S_2") (pintype "bidirectional"))
      (node (ref "SJ1") (pin "2") (pinfunction "2_2") (pintype "passive"))
      (node (ref "U1") (pin "1") (pinfunction "VIN_1") (pintype "power_in"))
      (node (ref "U3") (pin "6") (pinfunction "VOUT_6") (pintype "output"))
    )
    (net (code "46") (name "VINUSB") (class "Default")
      (node (ref "D2") (pin "4") (pinfunction "P$4_4") (pintype "passive"))
      (node (ref "F2") (pin "1") (pinfunction "1_1") (pintype "bidirectional"))
      (node (ref "USB1") (pin "1") (pinfunction "VCC_1") (pintype "bidirectional"))
    )
    (net (code "47") (name "VUSB") (class "Default")
      (node (ref "C1") (pin "2") (pinfunction "2_2") (pintype "passive"))
      (node (ref "F2") (pin "2") (pinfunction "2_2") (pintype "bidirectional"))
      (node (ref "R9") (pin "1") (pinfunction "1_1") (pintype "passive"))
      (node (ref "U3") (pin "1") (pinfunction "VIN_1") (pintype "input"))
    )
    (net (code "48") (name "unconnected-(U2-PadGPIO0)") (class "Default")
      (node (ref "U2") (pin "GPIO0") (pinfunction "GPIO0_GPIO0") (pintype "bidirectional"))
    )
    (net (code "49") (name "unconnected-(U2-PadGPIO1)") (class "Default")
      (node (ref "U2") (pin "GPIO1") (pinfunction "GPIO1_GPIO1") (pintype "bidirectional"))
    )
    (net (code "50") (name "unconnected-(U2-PadGPIO2)") (class "Default")
      (node (ref "U2") (pin "GPIO2") (pinfunction "GPIO2_GPIO2") (pintype "bidirectional"))
    )
    (net (code "51") (name "unconnected-(U2-PadGPIO3)") (class "Default")
      (node (ref "U2") (pin "GPIO3") (pinfunction "GPIO3_GPIO3") (pintype "bidirectional"))
    )
    (net (code "52") (name "unconnected-(U2-PadGPIO4)") (class "Default")
      (node (ref "U2") (pin "GPIO4") (pinfunction "GPIO4_GPIO4") (pintype "bidirectional"))
    )
    (net (code "53") (name "unconnected-(U2-PadGPIO5)") (class "Default")
      (node (ref "U2") (pin "GPIO5") (pinfunction "GPIO5_GPIO5") (pintype "bidirectional"))
    )
    (net (code "54") (name "unconnected-(U2-PadGPIO6)") (class "Default")
      (node (ref "U2") (pin "GPIO6") (pinfunction "GPIO6_GPIO6") (pintype "bidirectional"))
    )
    (net (code "55") (name "unconnected-(U2-PadGPIO7)") (class "Default")
      (node (ref "U2") (pin "GPIO7") (pinfunction "GPIO7_GPIO7") (pintype "bidirectional"))
    )
    (net (code "56") (name "unconnected-(U2-PadGPIO8)") (class "Default")
      (node (ref "U2") (pin "GPIO8") (pinfunction "GPIO8_GPIO8") (pintype "bidirectional"))
    )
    (net (code "57") (name "unconnected-(U2-PadGPIO9)") (class "Default")
      (node (ref "U2") (pin "GPIO9") (pinfunction "GPIO9_GPIO9") (pintype "bidirectional"))
    )
    (net (code "58") (name "unconnected-(U2-PadGPIO10)") (class "Default")
      (node (ref "U2") (pin "GPIO10") (pinfunction "GPIO10_GPIO10") (pintype "bidirectional"))
    )
    (net (code "59") (name "unconnected-(U2-PadGPIO11)") (class "Default")
      (node (ref "U2") (pin "GPIO11") (pinfunction "GPIO11_GPIO11") (pintype "bidirectional"))
    )
    (net (code "60") (name "unconnected-(U2-PadGPIO12)") (class "Default")
      (node (ref "U2") (pin "GPIO12") (pinfunction "GPIO12_GPIO12") (pintype "bidirectional"))
    )
    (net (code "61") (name "unconnected-(U2-PadGPIO13)") (class "Default")
      (node (ref "U2") (pin "GPIO13") (pinfunction "GPIO13_GPIO13") (pintype "bidirectional"))
    )
    (net (code "62") (name "unconnected-(U2-PadRFL)") (class "Default")
      (node (ref "U2") (pin "RFL") (pinfunction "RFL_RFL") (pintype "bidirectional"))
    )
    (net (code "63") (name "unconnected-(U2-PadUART_CTS)") (class "Default")
      (node (ref "U2") (pin "UART_CTS") (pinfunction "UART_CTS_UART_CTS") (pintype "bidirectional"))
    )
    (net (code "64") (name "unconnected-(U2-PadUART_RTS)") (class "Default")
      (node (ref "U2") (pin "UART_RTS") (pinfunction "UART_RTS_UART_RTS") (pintype "bidirectional"))
    )
    (net (code "65") (name "unconnected-(U3-NC-Pad4)") (class "Default")
      (node (ref "U3") (pin "4") (pinfunction "NC_4") (pintype "no_connect"))
    )
    (net (code "66") (name "unconnected-(U4-PA02(AIN0{slash}DAC)-Pad3)") (class "Default")
      (node (ref "U4") (pin "3") (pinfunction "PA02(AIN0/DAC)_3") (pintype "bidirectional"))
    )
    (net (code "67") (name "unconnected-(U4-PA03(AIN1{slash}REFA)-Pad4)") (class "Default")
      (node (ref "U4") (pin "4") (pinfunction "PA03(AIN1/REFA)_4") (pintype "bidirectional"))
    )
    (net (code "68") (name "unconnected-(U4-PA12(I2C{slash}SER2:0+)-Pad21)") (class "Default")
      (node (ref "U4") (pin "21") (pinfunction "PA12(I2C/SER2:0+)_21") (pintype "bidirectional"))
    )
    (net (code "69") (name "unconnected-(U4-PA14(XIN{slash}SER2:2+)-Pad23)") (class "Default")
      (node (ref "U4") (pin "23") (pinfunction "PA14(XIN/SER2:2+)_23") (pintype "bidirectional"))
    )
    (net (code "70") (name "unconnected-(U4-PA17(I2C{slash}SER1:1+)-Pad26)") (class "Default")
      (node (ref "U4") (pin "26") (pinfunction "PA17(I2C/SER1:1+)_26") (pintype "bidirectional"))
    )
    (net (code "71") (name "unconnected-(U4-PA18(SER1:2+)-Pad27)") (class "Default")
      (node (ref "U4") (pin "27") (pinfunction "PA18(SER1:2+)_27") (pintype "bidirectional"))
    )
    (net (code "72") (name "unconnected-(U4-PA19(SER1:3+)-Pad28)") (class "Default")
      (node (ref "U4") (pin "28") (pinfunction "PA19(SER1:3+)_28") (pintype "bidirectional"))
    )
    (net (code "73") (name "unconnected-(U4-PA20(SER5:2+)-Pad29)") (class "Default")
      (node (ref "U4") (pin "29") (pinfunction "PA20(SER5:2+)_29") (pintype "bidirectional"))
    )
    (net (code "74") (name "unconnected-(U4-PA21(SER5:3+)-Pad30)") (class "Default")
      (node (ref "U4") (pin "30") (pinfunction "PA21(SER5:3+)_30") (pintype "bidirectional"))
    )
    (net (code "75") (name "unconnected-(U4-PB02(AIN10{slash}SER5:0)-Pad47)") (class "Default")
      (node (ref "U4") (pin "47") (pinfunction "PB02(AIN10/SER5:0)_47") (pintype "bidirectional"))
    )
    (net (code "76") (name "unconnected-(USB1-ID-Pad4)") (class "Default")
      (node (ref "USB1") (pin "4") (pinfunction "ID_4") (pintype "bidirectional"))
    )
  )
)
